# DC_Converter.net
KiCad netlist of a schematic drawn in Altium Designer
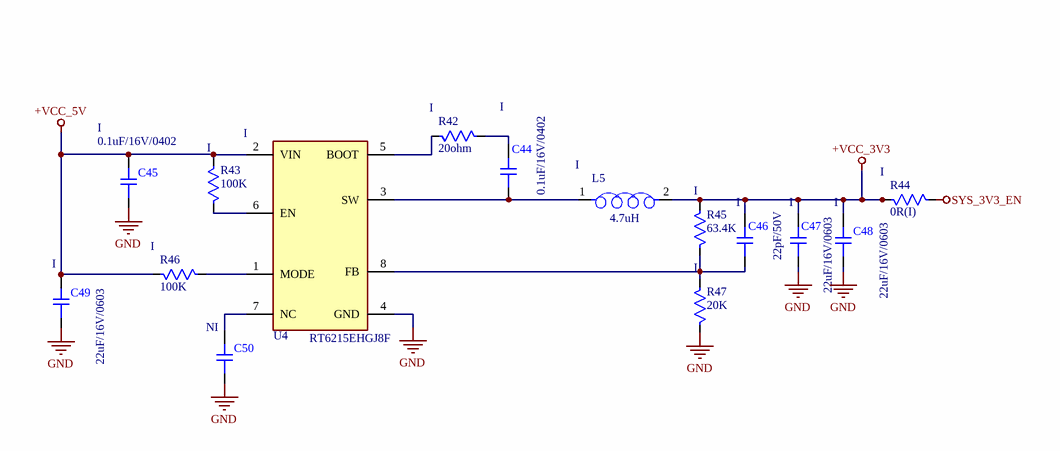
[diagram p0: DC Converter.SchDoc]

(export (version "E")
  (design (tool "Eeschema 10.0.6"))
  (components
    (comp (ref "C44")
      (value "0.1uF/16V/0402")
      (footprint "C0402")
      (fields (field (name "BOM") "I"))
      (libsource (lib "AMIDA7") (part "Cap"))
    )
    (comp (ref "C45")
      (value "0.1uF/16V/0402")
      (footprint "C0402")
      (fields (field (name "BOM") "I"))
      (libsource (lib "AMIDA7") (part "Cap"))
    )
    (comp (ref "C46")
      (value "22pF/50V")
      (footprint "C0402")
      (fields (field (name "BOM") "I"))
      (libsource (lib "AMIDA7") (part "Cap"))
    )
    (comp (ref "C47")
      (value "22uF/16V/0603")
      (footprint "C0603")
      (fields (field (name "BOM") "I"))
      (libsource (lib "AMIDA7") (part "Cap"))
    )
    (comp (ref "C48")
      (value "22uF/16V/0603")
      (footprint "C0603")
      (fields (field (name "BOM") "I"))
      (libsource (lib "AMIDA7") (part "Cap"))
    )
    (comp (ref "C49")
      (value "22uF/16V/0603")
      (footprint "C0603")
      (fields (field (name "BOM") "I"))
      (libsource (lib "AMIDA7") (part "Cap"))
    )
    (comp (ref "C50")
      (value "NI")
      (footprint "C0402")
      (description "3.9nF/16V")
      (fields (field (name "BOM") "NI"))
      (libsource (lib "AMIDA7") (part "Cap"))
    )
    (comp (ref "L5")
      (value "4.7uH")
      (footprint "IND-HPI0402")
      (description "3L COILS/HPI0402-4R7M")
      (fields (field (name "BOM") "I"))
      (libsource (lib "AMIDA7") (part "INDUCTOR"))
    )
    (comp (ref "R42")
      (value "20ohm")
      (footprint "R0402")
      (fields (field (name "BOM") "I"))
      (libsource (lib "AMIDA7") (part "Res"))
    )
    (comp (ref "R43")
      (value "100K")
      (footprint "R0402")
      (fields (field (name "BOM") "I"))
      (libsource (lib "AMIDA7") (part "Res"))
    )
    (comp (ref "R44")
      (value "0R(I)")
      (footprint "R0402")
      (fields (field (name "BOM") "I"))
      (libsource (lib "AMIDA7") (part "Res"))
    )
    (comp (ref "R45")
      (value "63.4K")
      (footprint "R0603")
      (fields (field (name "BOM") "I"))
      (libsource (lib "AMIDA7") (part "Res"))
    )
    (comp (ref "R46")
      (value "100K")
      (footprint "R0402")
      (fields (field (name "BOM") "I"))
      (libsource (lib "AMIDA7") (part "Res"))
    )
    (comp (ref "R47")
      (value "20K")
      (footprint "R0603")
      (fields (field (name "BOM") "I"))
      (libsource (lib "AMIDA7") (part "Res"))
    )
    (comp (ref "U4")
      (value "RT6215EHGJ8F")
      (footprint "SOT65P280X100-8N")
      (fields (field (name "BOM") "I"))
      (libsource (lib "AMIDA7") (part "RT6215EHGJ8F"))
    )
  )
  (nets
    (net (code "1") (name "+VCC_3V3") (class "Default")
      (node (ref "C46") (pin "2") (pinfunction "2_2") (pintype "passive"))
      (node (ref "C47") (pin "2") (pinfunction "2_2") (pintype "passive"))
      (node (ref "C48") (pin "2") (pinfunction "2_2") (pintype "passive"))
      (node (ref "L5") (pin "2") (pinfunction "2_2") (pintype "passive"))
      (node (ref "R44") (pin "1") (pinfunction "1_1") (pintype "passive"))
      (node (ref "R45") (pin "1") (pinfunction "1_1") (pintype "passive"))
    )
    (net (code "2") (name "+VCC_5V") (class "Default")
      (node (ref "C45") (pin "2") (pinfunction "2_2") (pintype "passive"))
      (node (ref "C49") (pin "2") (pinfunction "2_2") (pintype "passive"))
      (node (ref "R43") (pin "2") (pinfunction "2_2") (pintype "passive"))
      (node (ref "R46") (pin "2") (pinfunction "2_2") (pintype "passive"))
      (node (ref "U4") (pin "2") (pinfunction "VIN_2") (pintype "passive"))
    )
    (net (code "3") (name "GND") (class "Default")
      (node (ref "C45") (pin "1") (pinfunction "1_1") (pintype "passive"))
      (node (ref "C47") (pin "1") (pinfunction "1_1") (pintype "passive"))
      (node (ref "C48") (pin "1") (pinfunction "1_1") (pintype "passive"))
      (node (ref "C49") (pin "1") (pinfunction "1_1") (pintype "passive"))
      (node (ref "C50") (pin "1") (pinfunction "1_1") (pintype "passive"))
      (node (ref "R47") (pin "2") (pinfunction "2_2") (pintype "passive"))
      (node (ref "U4") (pin "4") (pinfunction "GND_4") (pintype "passive"))
    )
    (net (code "4") (name "Net-(C44-Pad2)") (class "Default")
      (node (ref "C44") (pin "2") (pinfunction "2_2") (pintype "passive"))
      (node (ref "R42") (pin "1") (pinfunction "1_1") (pintype "passive"))
    )
    (net (code "5") (name "Net-(U4-BOOT)") (class "Default")
      (node (ref "R42") (pin "2") (pinfunction "2_2") (pintype "passive"))
      (node (ref "U4") (pin "5") (pinfunction "BOOT_5") (pintype "passive"))
    )
    (net (code "6") (name "Net-(U4-EN)") (class "Default")
      (node (ref "R43") (pin "1") (pinfunction "1_1") (pintype "passive"))
      (node (ref "U4") (pin "6") (pinfunction "EN_6") (pintype "passive"))
    )
    (net (code "7") (name "Net-(U4-FB)") (class "Default")
      (node (ref "C46") (pin "1") (pinfunction "1_1") (pintype "passive"))
      (node (ref "R45") (pin "2") (pinfunction "2_2") (pintype "passive"))
      (node (ref "R47") (pin "1") (pinfunction "1_1") (pintype "passive"))
      (node (ref "U4") (pin "8") (pinfunction "FB_8") (pintype "passive"))
    )
    (net (code "8") (name "Net-(U4-MODE)") (class "Default")
      (node (ref "R46") (pin "1") (pinfunction "1_1") (pintype "passive"))
      (node (ref "U4") (pin "1") (pinfunction "MODE_1") (pintype "passive"))
    )
    (net (code "9") (name "Net-(U4-NC)") (class "Default")
      (node (ref "C50") (pin "2") (pinfunction "2_2") (pintype "passive"))
      (node (ref "U4") (pin "7") (pinfunction "NC_7") (pintype "passive"))
    )
    (net (code "10") (name "Net-(U4-SW)") (class "Default")
      (node (ref "C44") (pin "1") (pinfunction "1_1") (pintype "passive"))
      (node (ref "L5") (pin "1") (pinfunction "1_1") (pintype "passive"))
      (node (ref "U4") (pin "3") (pinfunction "SW_3") (pintype "passive"))
    )
    (net (code "11") (name "SYS_3V3_EN") (class "Default")
      (node (ref "R44") (pin "2") (pinfunction "2_2") (pintype "passive"))
    )
  )
)
